# DC-DC.net
KiCad netlist of a schematic drawn in EAGLE
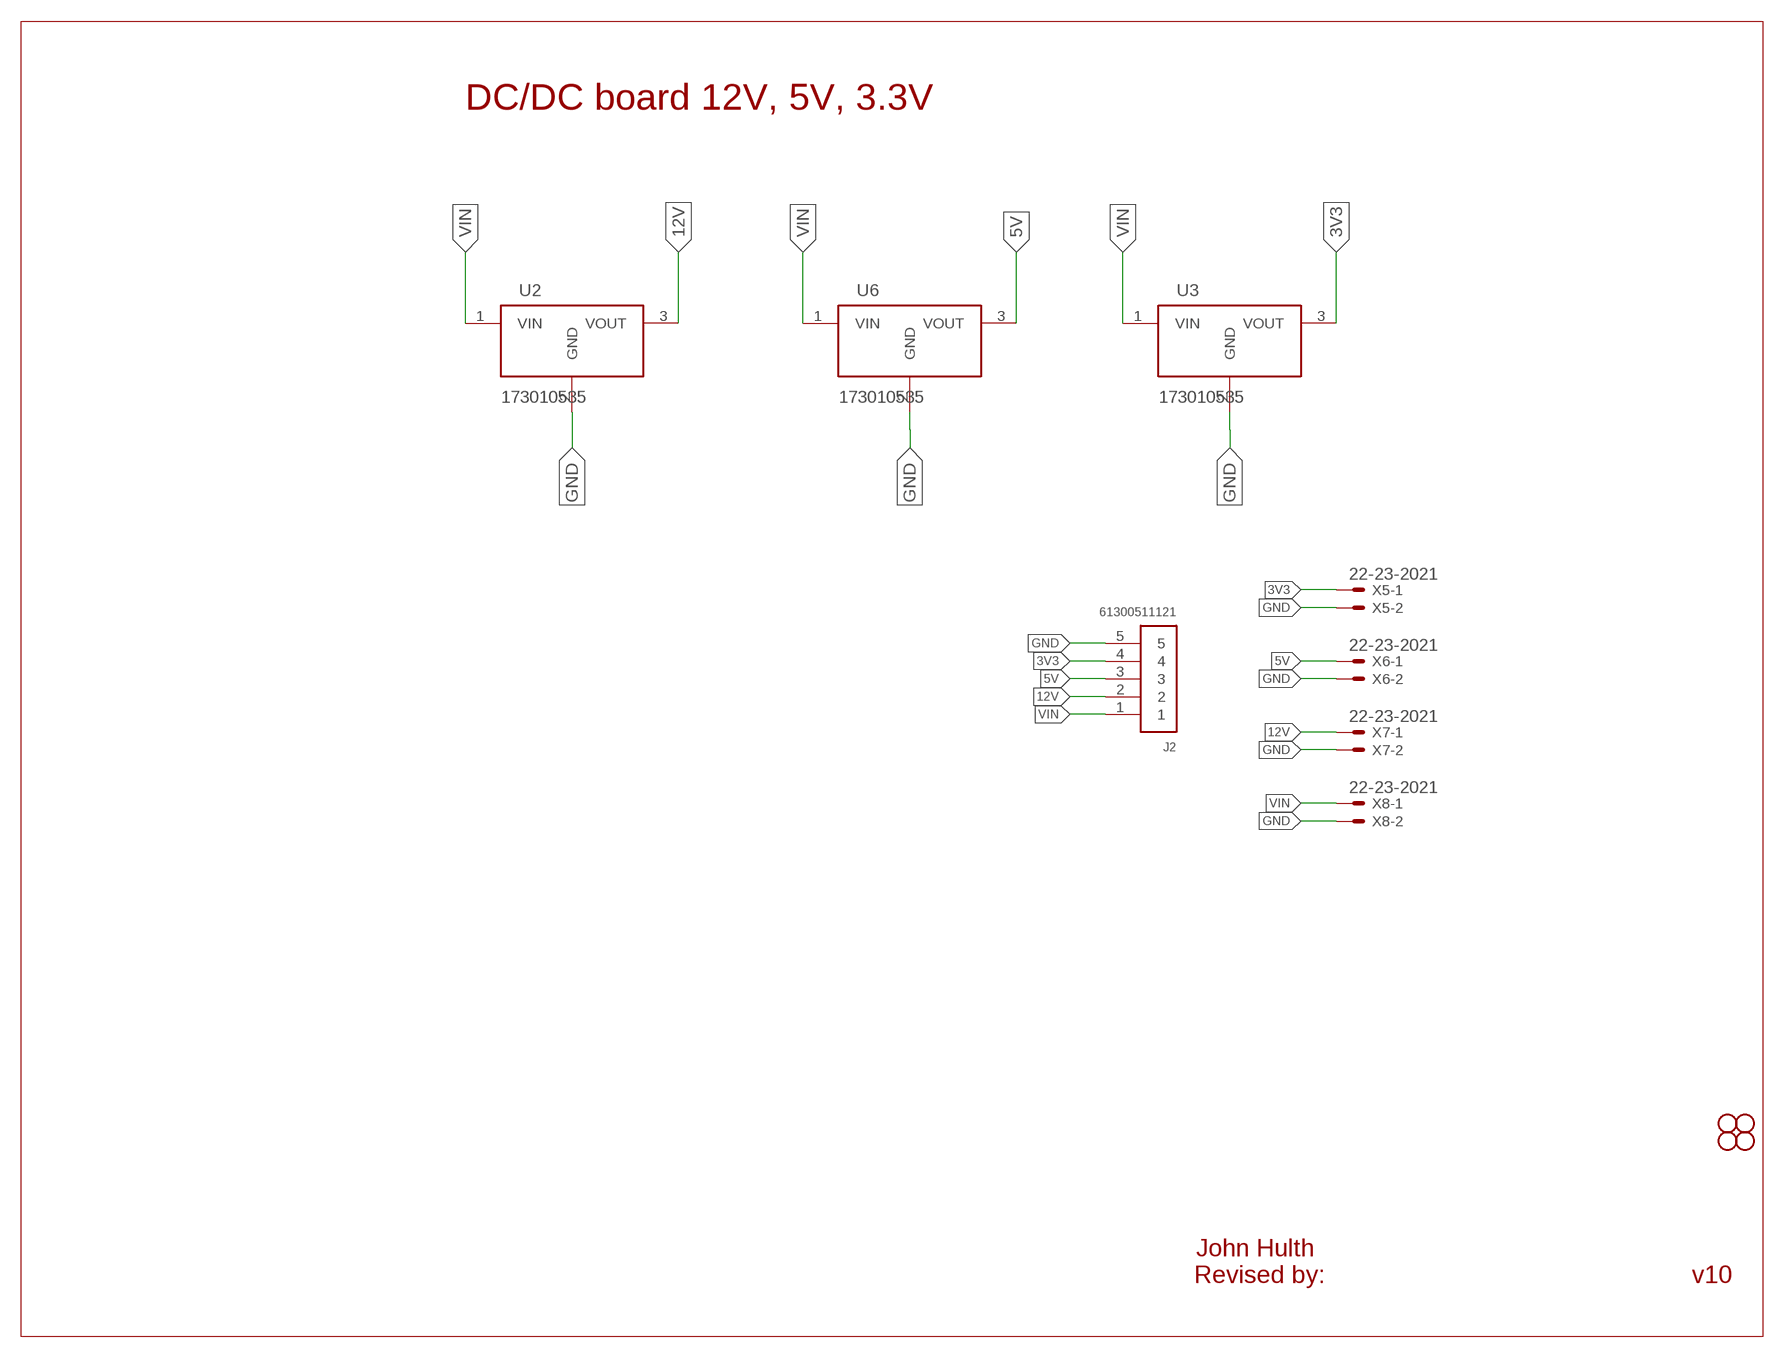
[diagram p0: schematic, sheet 1]

(export (version "E")
  (design (tool "Eeschema 10.0.6"))
  (components
    (comp (ref "J2")
      (value "61300511121")
      (footprint "eagle-import:61300511121")
      (fields
        (field (name "DIGI_KEY_PART_NUMBER") "732-5318-ND")
        (field (name "MANUFACTURER") "Wurth Electronics Inc.")
        (field (name "CREATED_BY") "PCBLayout.com")
      )
      (libsource (lib "eagle-import") (part "61300511121"))
    )
    (comp (ref "JP1")
      (value "STAND-OFF")
      (footprint "eagle-import:STAND-OFF")
      (libsource (lib "eagle-import") (part "STAND-OFF"))
    )
    (comp (ref "JP4")
      (value "STAND-OFF")
      (footprint "eagle-import:STAND-OFF")
      (libsource (lib "eagle-import") (part "STAND-OFF"))
    )
    (comp (ref "JP5")
      (value "STAND-OFF")
      (footprint "eagle-import:STAND-OFF")
      (libsource (lib "eagle-import") (part "STAND-OFF"))
    )
    (comp (ref "JP6")
      (value "STAND-OFF")
      (footprint "eagle-import:STAND-OFF")
      (libsource (lib "eagle-import") (part "STAND-OFF"))
    )
    (comp (ref "U2")
      (value "173010535")
      (footprint "eagle-import:173010535")
      (fields
        (field (name "DIGIKEY_PARTNO") "732-173010535-ND")
        (field (name "MANUFACTURER") "Würth Elektronik")
        (field (name "CREATED_BY") "PCBLayout.com")
      )
      (libsource (lib "eagle-import") (part "173010535"))
    )
    (comp (ref "U3")
      (value "173010535")
      (footprint "eagle-import:173010535")
      (fields
        (field (name "DIGIKEY_PARTNO") "732-173010535-ND")
        (field (name "MANUFACTURER") "Würth Elektronik")
        (field (name "CREATED_BY") "PCBLayout.com")
      )
      (libsource (lib "eagle-import") (part "173010535"))
    )
    (comp (ref "U6")
      (value "173010535")
      (footprint "eagle-import:173010535")
      (fields
        (field (name "DIGIKEY_PARTNO") "732-173010535-ND")
        (field (name "MANUFACTURER") "Würth Elektronik")
        (field (name "CREATED_BY") "PCBLayout.com")
      )
      (libsource (lib "eagle-import") (part "173010535"))
    )
    (comp (ref "X5")
      (value "22-23-2021")
      (footprint "eagle-import:22-23-2021")
      (fields (field (name "MF") "MOLEX"))
      (libsource (lib "eagle-import") (part "22-23-2021"))
    )
    (comp (ref "X6")
      (value "22-23-2021")
      (footprint "eagle-import:22-23-2021")
      (fields (field (name "MF") "MOLEX"))
      (libsource (lib "eagle-import") (part "22-23-2021"))
    )
    (comp (ref "X7")
      (value "22-23-2021")
      (footprint "eagle-import:22-23-2021")
      (fields (field (name "MF") "MOLEX"))
      (libsource (lib "eagle-import") (part "22-23-2021"))
    )
    (comp (ref "X8")
      (value "22-23-2021")
      (footprint "eagle-import:22-23-2021")
      (fields (field (name "MF") "MOLEX"))
      (libsource (lib "eagle-import") (part "22-23-2021"))
    )
  )
  (nets
    (net (code "1") (name "3V3") (class "Default")
      (node (ref "J2") (pin "4") (pinfunction "4_4") (pintype "passive"))
      (node (ref "U3") (pin "3") (pinfunction "VOUT_3") (pintype "power_in"))
      (node (ref "X5") (pin "1") (pinfunction "S_1") (pintype "passive"))
    )
    (net (code "2") (name "5V") (class "Default")
      (node (ref "J2") (pin "3") (pinfunction "3_3") (pintype "passive"))
      (node (ref "U6") (pin "3") (pinfunction "VOUT_3") (pintype "power_in"))
      (node (ref "X6") (pin "1") (pinfunction "S_1") (pintype "passive"))
    )
    (net (code "3") (name "12V") (class "Default")
      (node (ref "J2") (pin "2") (pinfunction "2_2") (pintype "passive"))
      (node (ref "U2") (pin "3") (pinfunction "VOUT_3") (pintype "power_in"))
      (node (ref "X7") (pin "1") (pinfunction "S_1") (pintype "passive"))
    )
    (net (code "4") (name "GND") (class "Default")
      (node (ref "J2") (pin "5") (pinfunction "5_5") (pintype "passive"))
      (node (ref "U2") (pin "2") (pinfunction "GND_2") (pintype "power_in"))
      (node (ref "U3") (pin "2") (pinfunction "GND_2") (pintype "power_in"))
      (node (ref "U6") (pin "2") (pinfunction "GND_2") (pintype "power_in"))
      (node (ref "X5") (pin "2") (pinfunction "S_2") (pintype "passive"))
      (node (ref "X6") (pin "2") (pinfunction "S_2") (pintype "passive"))
      (node (ref "X7") (pin "2") (pinfunction "S_2") (pintype "passive"))
      (node (ref "X8") (pin "2") (pinfunction "S_2") (pintype "passive"))
    )
    (net (code "5") (name "VIN") (class "Default")
      (node (ref "J2") (pin "1") (pinfunction "1_1") (pintype "passive"))
      (node (ref "U2") (pin "1") (pinfunction "VIN_1") (pintype "power_in"))
      (node (ref "U3") (pin "1") (pinfunction "VIN_1") (pintype "power_in"))
      (node (ref "U6") (pin "1") (pinfunction "VIN_1") (pintype "power_in"))
      (node (ref "X8") (pin "1") (pinfunction "S_1") (pintype "passive"))
    )
  )
)
